# DM1097_EthernetSchDoc.net
KiCad netlist of a schematic drawn in Altium Designer
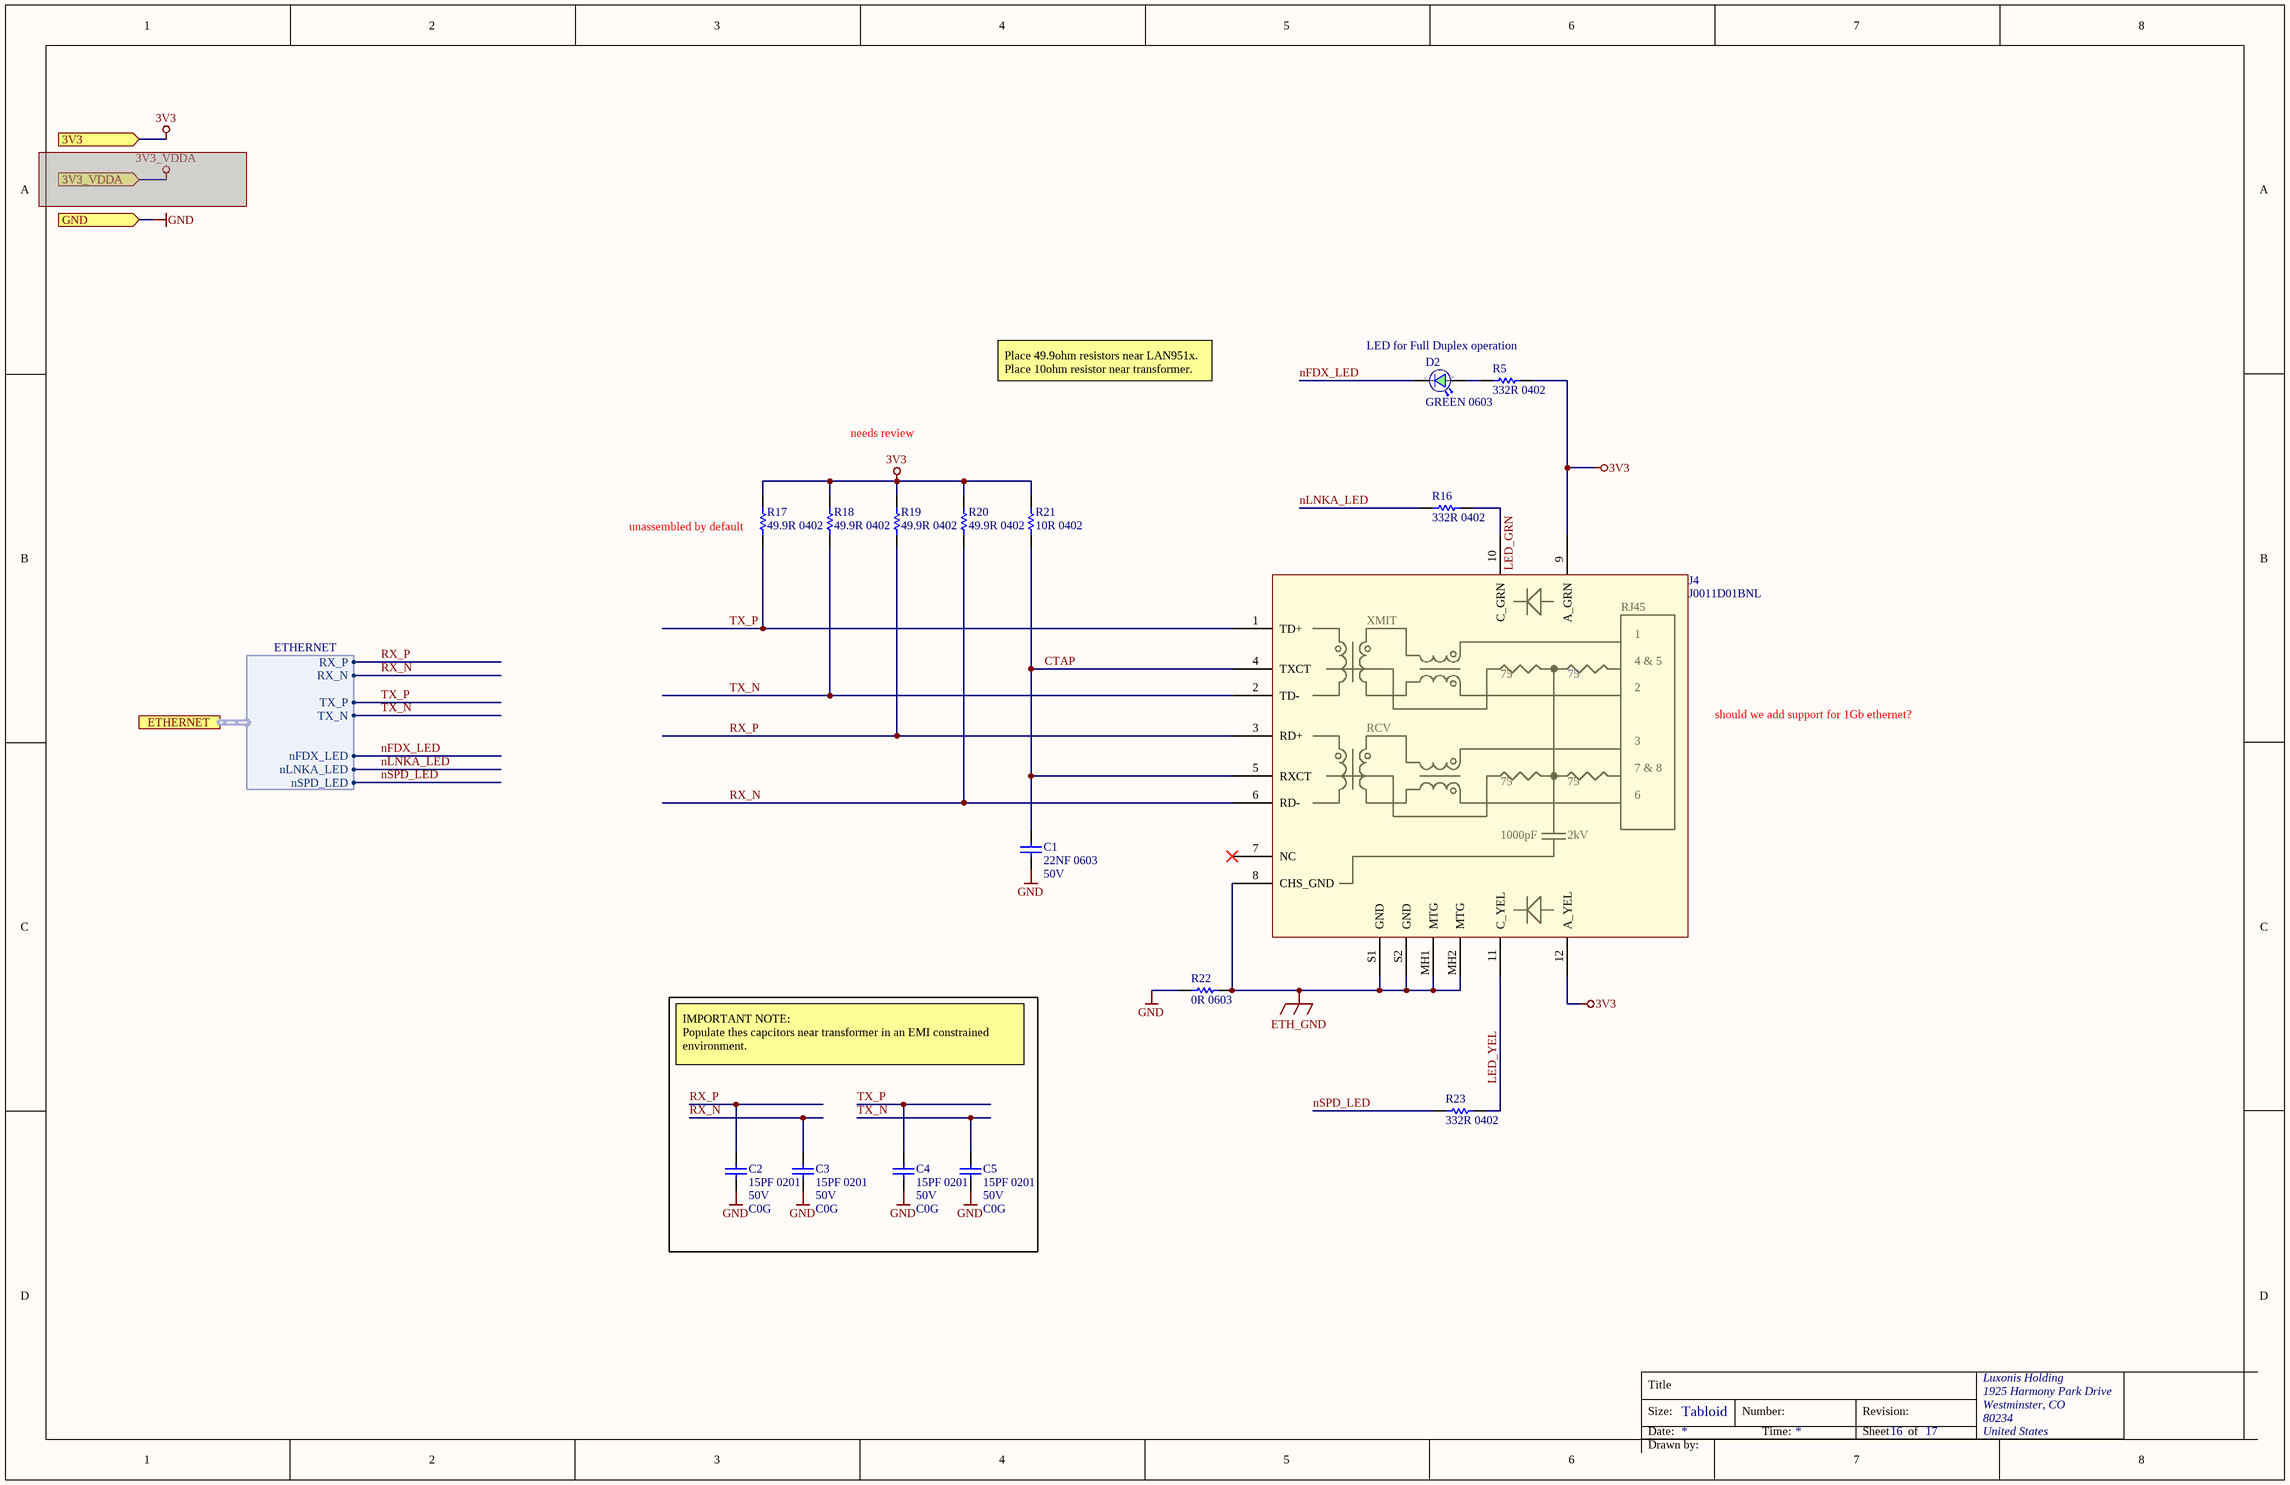
[diagram p0: DM1097_EthernetSchDoc.SchDoc]

(export (version "E")
  (design (tool "Eeschema 10.0.6"))
  (components
    (comp (ref "C1")
      (value "22NF 0603")
      (footprint "CAP_Altium_Vault_Generic:CAPC0603(1608)100_N")
      (description "CAP CER 0.022UF 50V X7R 0603")
      (fields (field (name "TOLERANCE") "10%") (field (name "VOLTAGE") "50V"))
      (libsource (lib "LuxonisMaster") (part "C0603C223K5RACTU"))
    )
    (comp (ref "C2")
      (value "15PF 0201")
      (footprint "CAP_Altium_Vault_Generic:CAPC0201(0603)33_L")
      (description "CAP CER 15PF 50V C0G/NP0 0201")
      (fields
        (field (name "TOLERANCE") "5%")
        (field (name "VOLTAGE") "50V")
        (field (name "DIELECTRIC") "C0G")
      )
      (libsource (lib "LuxonisMaster") (part "GRM0335C1H150JA01D"))
    )
    (comp (ref "C3")
      (value "15PF 0201")
      (footprint "CAP_Altium_Vault_Generic:CAPC0201(0603)33_L")
      (description "CAP CER 15PF 50V C0G/NP0 0201")
      (fields
        (field (name "TOLERANCE") "5%")
        (field (name "VOLTAGE") "50V")
        (field (name "DIELECTRIC") "C0G")
      )
      (libsource (lib "LuxonisMaster") (part "GRM0335C1H150JA01D"))
    )
    (comp (ref "C4")
      (value "15PF 0201")
      (footprint "CAP_Altium_Vault_Generic:CAPC0201(0603)33_L")
      (description "CAP CER 15PF 50V C0G/NP0 0201")
      (fields
        (field (name "TOLERANCE") "5%")
        (field (name "VOLTAGE") "50V")
        (field (name "DIELECTRIC") "C0G")
      )
      (libsource (lib "LuxonisMaster") (part "GRM0335C1H150JA01D"))
    )
    (comp (ref "C5")
      (value "15PF 0201")
      (footprint "CAP_Altium_Vault_Generic:CAPC0201(0603)33_L")
      (description "CAP CER 15PF 50V C0G/NP0 0201")
      (fields
        (field (name "TOLERANCE") "5%")
        (field (name "VOLTAGE") "50V")
        (field (name "DIELECTRIC") "C0G")
      )
      (libsource (lib "LuxonisMaster") (part "GRM0335C1H150JA01D"))
    )
    (comp (ref "D2")
      (value "GREEN 0603")
      (footprint "LuxonisMaster:SML_D1xx8W")
      (description "LED GREEN DIFFUSED 0603 SMD Green 572nm LED Indication - Discrete 2.2V 0603 (1608 Metric)")
      (fields (field (name "MANUFACTURER") "Rohm") (field (name "MANUFACTURER PART NUMBER") "SML-D12M8WT86"))
      (libsource (lib "LuxonisMaster") (part "SML-D12M8WT86"))
    )
    (comp (ref "J4")
      (value "J0011D01BNL")
      (footprint "LuxonisMaster:J0011D01BNL")
      (description "CONN MAGJACK 1PORT 100 BASE-TX 1 Port RJ45 Magjack Connector Through Hole 10/100 Base-TX, AutoMDIX")
      (libsource (lib "LuxonisMaster") (part "J0011D01BNL"))
    )
    (comp (ref "R5")
      (value "332R 0402")
      (footprint "RES_Altium_Vault_Generic:RESC0402(1005)_N")
      (description "RES SMD 332 OHM 1% 1/16W 0402")
      (fields (field (name "TOLERANCE") "1%"))
      (libsource (lib "LuxonisMaster") (part "RC0402FR-07332RL"))
    )
    (comp (ref "R16")
      (value "332R 0402")
      (footprint "RES_Altium_Vault_Generic:RESC0402(1005)_N")
      (description "RES SMD 332 OHM 1% 1/16W 0402")
      (fields (field (name "TOLERANCE") "1%"))
      (libsource (lib "LuxonisMaster") (part "RC0402FR-07332RL"))
    )
    (comp (ref "R17")
      (value "49.9R 0402")
      (footprint "RES_Altium_Vault_Generic:RESC0402(1005)_N")
      (description "RES SMD 49.9 OHM 1% 1/16W 0402")
      (fields (field (name "TOLERANCE") "1%"))
      (libsource (lib "LuxonisMaster") (part "RC0402FR-0749R9L"))
    )
    (comp (ref "R18")
      (value "49.9R 0402")
      (footprint "RES_Altium_Vault_Generic:RESC0402(1005)_N")
      (description "RES SMD 49.9 OHM 1% 1/16W 0402")
      (fields (field (name "TOLERANCE") "1%"))
      (libsource (lib "LuxonisMaster") (part "RC0402FR-0749R9L"))
    )
    (comp (ref "R19")
      (value "49.9R 0402")
      (footprint "RES_Altium_Vault_Generic:RESC0402(1005)_N")
      (description "RES SMD 49.9 OHM 1% 1/16W 0402")
      (fields (field (name "TOLERANCE") "1%"))
      (libsource (lib "LuxonisMaster") (part "RC0402FR-0749R9L"))
    )
    (comp (ref "R20")
      (value "49.9R 0402")
      (footprint "RES_Altium_Vault_Generic:RESC0402(1005)_N")
      (description "RES SMD 49.9 OHM 1% 1/16W 0402")
      (fields (field (name "TOLERANCE") "1%"))
      (libsource (lib "LuxonisMaster") (part "RC0402FR-0749R9L"))
    )
    (comp (ref "R21")
      (value "10R 0402")
      (footprint "RES_Altium_Vault_Generic:RESC0402(1005)_N")
      (description "RES SMD 10 OHM 1% 1/16W 0402")
      (fields (field (name "TOLERANCE") "1%"))
      (libsource (lib "LuxonisMaster") (part "RC0402FR-0710RL"))
    )
    (comp (ref "R22")
      (value "0R 0603")
      (footprint "RES_Altium_Vault_Generic:RESC0603(1608)_N")
      (fields (field (name "TOLERANCE") "5%"))
      (libsource (lib "LuxonisMaster") (part "CRCW06030000Z0EA"))
    )
    (comp (ref "R23")
      (value "332R 0402")
      (footprint "RES_Altium_Vault_Generic:RESC0402(1005)_N")
      (description "RES SMD 332 OHM 1% 1/16W 0402")
      (fields (field (name "TOLERANCE") "1%"))
      (libsource (lib "LuxonisMaster") (part "RC0402FR-07332RL"))
    )
  )
  (nets
    (net (code "2") (name "/CTAP") (class "Default")
      (node (ref "C1") (pin "2") (pinfunction "2_2") (pintype "passive"))
      (node (ref "J4") (pin "4") (pinfunction "TXCT_4") (pintype "passive"))
      (node (ref "J4") (pin "5") (pinfunction "RXCT_5") (pintype "passive"))
      (node (ref "R21") (pin "1") (pinfunction "1_1") (pintype "passive"))
    )
    (net (code "3") (name "/LED_GRN") (class "Default")
      (node (ref "J4") (pin "10") (pinfunction "C_GRN_10") (pintype "passive"))
      (node (ref "R16") (pin "2") (pinfunction "2_2") (pintype "passive"))
    )
    (net (code "4") (name "/LED_YEL") (class "Default")
      (node (ref "J4") (pin "11") (pinfunction "C_YEL_11") (pintype "passive"))
      (node (ref "R23") (pin "2") (pinfunction "2_2") (pintype "passive"))
    )
    (net (code "5") (name "/RX_N") (class "Default")
      (node (ref "C3") (pin "2") (pinfunction "2_2") (pintype "passive"))
      (node (ref "J4") (pin "6") (pinfunction "RD-_6") (pintype "passive"))
      (node (ref "R20") (pin "1") (pinfunction "1_1") (pintype "passive"))
    )
    (net (code "6") (name "/RX_P") (class "Default")
      (node (ref "C2") (pin "2") (pinfunction "2_2") (pintype "passive"))
      (node (ref "J4") (pin "3") (pinfunction "RD+_3") (pintype "passive"))
      (node (ref "R19") (pin "1") (pinfunction "1_1") (pintype "passive"))
    )
    (net (code "7") (name "/TX_N") (class "Default")
      (node (ref "C5") (pin "2") (pinfunction "2_2") (pintype "passive"))
      (node (ref "J4") (pin "2") (pinfunction "TD-_2") (pintype "passive"))
      (node (ref "R18") (pin "1") (pinfunction "1_1") (pintype "passive"))
    )
    (net (code "8") (name "/TX_P") (class "Default")
      (node (ref "C4") (pin "2") (pinfunction "2_2") (pintype "passive"))
      (node (ref "J4") (pin "1") (pinfunction "TD+_1") (pintype "passive"))
      (node (ref "R17") (pin "1") (pinfunction "1_1") (pintype "passive"))
    )
    (net (code "9") (name "/nFDX_LED") (class "Default")
      (node (ref "D2") (pin "1") (pinfunction "C_1") (pintype "passive"))
    )
    (net (code "10") (name "/nLNKA_LED") (class "Default")
      (node (ref "R16") (pin "1") (pinfunction "1_1") (pintype "passive"))
    )
    (net (code "11") (name "/nSPD_LED") (class "Default")
      (node (ref "R23") (pin "1") (pinfunction "1_1") (pintype "passive"))
    )
    (net (code "13") (name "3V3") (class "Default")
      (node (ref "J4") (pin "12") (pinfunction "A_YEL_12") (pintype "passive"))
      (node (ref "J4") (pin "9") (pinfunction "A_GRN_9") (pintype "passive"))
      (node (ref "R17") (pin "2") (pinfunction "2_2") (pintype "passive"))
      (node (ref "R18") (pin "2") (pinfunction "2_2") (pintype "passive"))
      (node (ref "R19") (pin "2") (pinfunction "2_2") (pintype "passive"))
      (node (ref "R20") (pin "2") (pinfunction "2_2") (pintype "passive"))
      (node (ref "R21") (pin "2") (pinfunction "2_2") (pintype "passive"))
      (node (ref "R5") (pin "2") (pinfunction "2_2") (pintype "passive"))
    )
    (net (code "15") (name "ETH_GND") (class "Default")
      (node (ref "J4") (pin "8") (pinfunction "CHS_GND_8") (pintype "passive"))
      (node (ref "J4") (pin "MH1") (pinfunction "MTG_MH1") (pintype "passive"))
      (node (ref "J4") (pin "MH2") (pinfunction "MTG_MH2") (pintype "passive"))
      (node (ref "J4") (pin "S1") (pinfunction "GND_S1") (pintype "passive"))
      (node (ref "J4") (pin "S2") (pinfunction "GND_S2") (pintype "passive"))
      (node (ref "R22") (pin "2") (pinfunction "2_2") (pintype "passive"))
    )
    (net (code "16") (name "GND") (class "Default")
      (node (ref "C1") (pin "1") (pinfunction "1_1") (pintype "passive"))
      (node (ref "C2") (pin "1") (pinfunction "1_1") (pintype "passive"))
      (node (ref "C3") (pin "1") (pinfunction "1_1") (pintype "passive"))
      (node (ref "C4") (pin "1") (pinfunction "1_1") (pintype "passive"))
      (node (ref "C5") (pin "1") (pinfunction "1_1") (pintype "passive"))
      (node (ref "R22") (pin "1") (pinfunction "1_1") (pintype "passive"))
    )
    (net (code "17") (name "Net-(D2-A)") (class "Default")
      (node (ref "D2") (pin "2") (pinfunction "A_2") (pintype "passive"))
      (node (ref "R5") (pin "1") (pinfunction "1_1") (pintype "passive"))
    )
    (net (code "18") (name "unconnected-(J4-NC-Pad7)") (class "Default")
      (node (ref "J4") (pin "7") (pinfunction "NC_7") (pintype "passive+no_connect"))
    )
    (net (code "19") (name "unconnected-(J4-Pad1)") (class "Default")
      (node (ref "J4") (pin "1") (pinfunction "1_1") (pintype "passive"))
    )
    (net (code "20") (name "unconnected-(J4-Pad2)") (class "Default")
      (node (ref "J4") (pin "2") (pinfunction "2_2") (pintype "passive"))
    )
  )
)
